# mlx90621_breakout.net
KiCad netlist of a schematic drawn in EAGLE
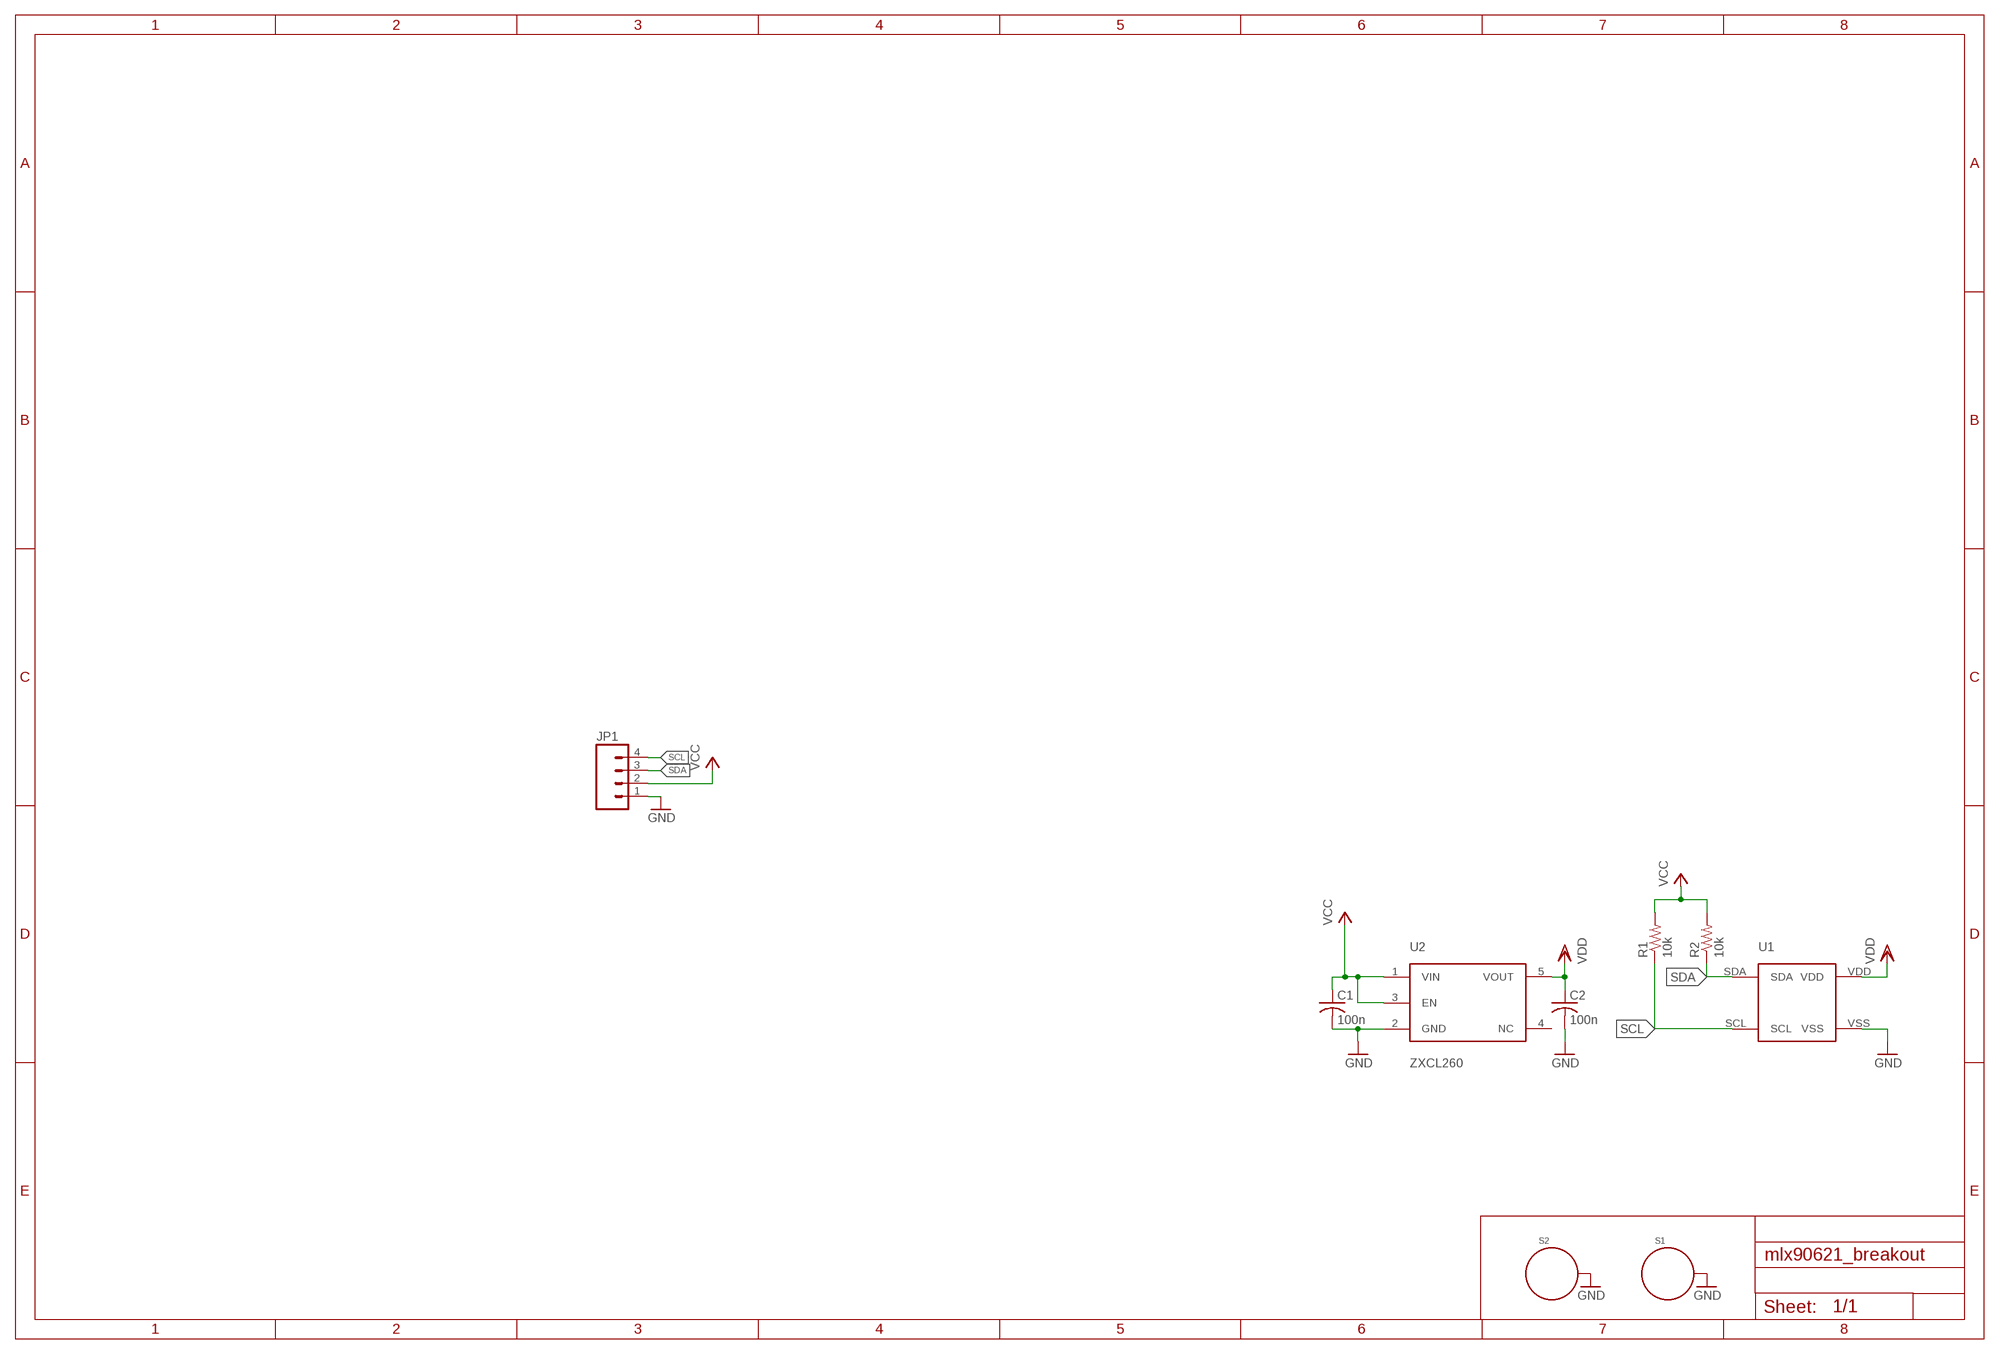
[diagram p0: schematic, sheet 1]

(export (version "E")
  (design (tool "Eeschema 10.0.6"))
  (components
    (comp (ref "C1")
      (value "100n")
      (footprint "eagle-import:C0603")
      (libsource (lib "eagle-import") (part "C-USC0603"))
    )
    (comp (ref "C2")
      (value "100n")
      (footprint "eagle-import:C0603")
      (libsource (lib "eagle-import") (part "C-USC0603"))
    )
    (comp (ref "JP1")
      (value "M04PTH")
      (footprint "eagle-import:1X04")
      (libsource (lib "eagle-import") (part "M04PTH"))
    )
    (comp (ref "R1")
      (value "10k")
      (footprint "eagle-import:R0603")
      (libsource (lib "eagle-import") (part "R-US_R0603"))
    )
    (comp (ref "R2")
      (value "10k")
      (footprint "eagle-import:R0603")
      (libsource (lib "eagle-import") (part "R-US_R0603"))
    )
    (comp (ref "S1")
      (value "STANDOFF_ELECTRICAL")
      (footprint "eagle-import:STANDOFF-ELECTRICAL")
      (libsource (lib "eagle-import") (part "STANDOFF_ELECTRICAL"))
    )
    (comp (ref "S2")
      (value "STANDOFF_ELECTRICAL")
      (footprint "eagle-import:STANDOFF-ELECTRICAL")
      (libsource (lib "eagle-import") (part "STANDOFF_ELECTRICAL"))
    )
    (comp (ref "U1")
      (value "MLX90621BAD")
      (footprint "eagle-import:MLX90621")
      (libsource (lib "eagle-import") (part "MLX90621BAD"))
    )
    (comp (ref "U2")
      (value "ZXCL260")
      (footprint "eagle-import:VREG_SOT23-5")
      (libsource (lib "eagle-import") (part "ZXCL260"))
    )
  )
  (nets
    (net (code "1") (name "GND") (class "Default")
      (node (ref "C1") (pin "2") (pinfunction "2_2") (pintype "passive"))
      (node (ref "C2") (pin "2") (pinfunction "2_2") (pintype "passive"))
      (node (ref "JP1") (pin "1") (pinfunction "1_1") (pintype "passive"))
      (node (ref "S1") (pin "P1") (pinfunction "P$1_P1") (pintype "bidirectional"))
      (node (ref "S2") (pin "P1") (pinfunction "P$1_P1") (pintype "bidirectional"))
      (node (ref "U1") (pin "VSS") (pinfunction "VSS_VSS") (pintype "power_in"))
      (node (ref "U2") (pin "2") (pinfunction "GND_2") (pintype "bidirectional"))
    )
    (net (code "2") (name "SCL") (class "Default")
      (node (ref "JP1") (pin "4") (pinfunction "4_4") (pintype "passive"))
      (node (ref "R1") (pin "1") (pinfunction "1_1") (pintype "passive"))
      (node (ref "U1") (pin "SCL") (pinfunction "SCL_SCL") (pintype "input"))
    )
    (net (code "3") (name "SDA") (class "Default")
      (node (ref "JP1") (pin "3") (pinfunction "3_3") (pintype "passive"))
      (node (ref "R2") (pin "1") (pinfunction "1_1") (pintype "passive"))
      (node (ref "U1") (pin "SDA") (pinfunction "SDA_SDA") (pintype "bidirectional"))
    )
    (net (code "4") (name "VCC") (class "Default")
      (node (ref "C1") (pin "1") (pinfunction "1_1") (pintype "passive"))
      (node (ref "JP1") (pin "2") (pinfunction "2_2") (pintype "passive"))
      (node (ref "R1") (pin "2") (pinfunction "2_2") (pintype "passive"))
      (node (ref "R2") (pin "2") (pinfunction "2_2") (pintype "passive"))
      (node (ref "U2") (pin "1") (pinfunction "VIN_1") (pintype "bidirectional"))
      (node (ref "U2") (pin "3") (pinfunction "EN_3") (pintype "bidirectional"))
    )
    (net (code "5") (name "VDD") (class "Default")
      (node (ref "C2") (pin "1") (pinfunction "1_1") (pintype "passive"))
      (node (ref "U1") (pin "VDD") (pinfunction "VDD_VDD") (pintype "power_in"))
      (node (ref "U2") (pin "5") (pinfunction "VOUT_5") (pintype "bidirectional"))
    )
    (net (code "6") (name "unconnected-(U2-NC-Pad4)") (class "Default")
      (node (ref "U2") (pin "4") (pinfunction "NC_4") (pintype "bidirectional"))
    )
  )
)
